# Sensor.net
KiCad netlist of a schematic drawn in Altium Designer
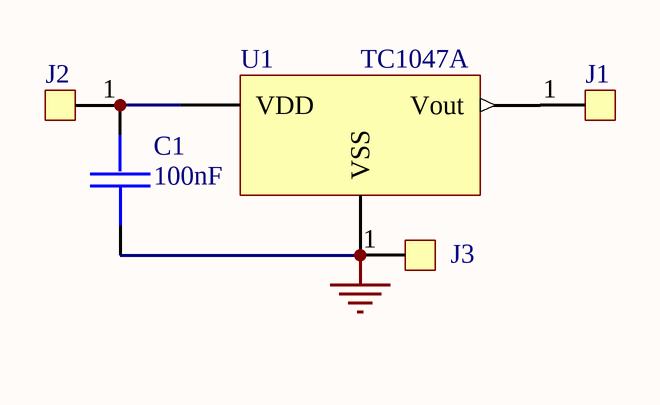
[diagram p0: Sensor.SCHDOC]

(export (version "E")
  (design (tool "Eeschema 10.0.6"))
  (components
    (comp (ref "C1")
      (value "100nF")
      (footprint "0805")
      (description "CAPACITOR SMD 0805 X7R  50 V 100 nF")
      (libsource (lib "CAPACITORES SMD0805") (part "100n"))
    )
    (comp (ref "J1")
      (value "CON3")
      (footprint "CON2")
      (description "PAD 2X2")
      (libsource (lib "CONECTORES") (part "CON3"))
    )
    (comp (ref "J2")
      (value "CON3")
      (footprint "CON2")
      (description "PAD 2X2")
      (libsource (lib "") (part "CON3_1"))
    )
    (comp (ref "J3")
      (value "CON3")
      (footprint "CON2")
      (description "PAD 2X2")
      (libsource (lib "CONECTORES") (part "CON3"))
    )
    (comp (ref "U1")
      (value "TC1047A")
      (footprint "SOT-23")
      (description "TC1047A SENSOR DE TEMPERATURA")
      (libsource (lib "CIRCUITOS INTEGRADOS SMD") (part "TC1047A"))
    )
  )
  (nets
    (net (code "1") (name "GND") (class "Default")
      (node (ref "C1") (pin "2") (pintype "passive"))
      (node (ref "J3") (pin "1") (pinfunction "1_1") (pintype "passive"))
      (node (ref "U1") (pin "3") (pinfunction "VSS_3") (pintype "passive"))
    )
    (net (code "2") (name "Net-(U1-VDD)") (class "Default")
      (node (ref "C1") (pin "1") (pintype "passive"))
      (node (ref "J2") (pin "1") (pinfunction "1_1") (pintype "passive"))
      (node (ref "U1") (pin "1") (pinfunction "VDD_1") (pintype "power_in"))
    )
    (net (code "3") (name "Net-(U1-Vout)") (class "Default")
      (node (ref "J1") (pin "1") (pinfunction "1_1") (pintype "passive"))
      (node (ref "U1") (pin "2") (pinfunction "Vout_2") (pintype "output"))
    )
  )
)
